# analog.net
KiCad netlist of a schematic drawn in Altium Designer
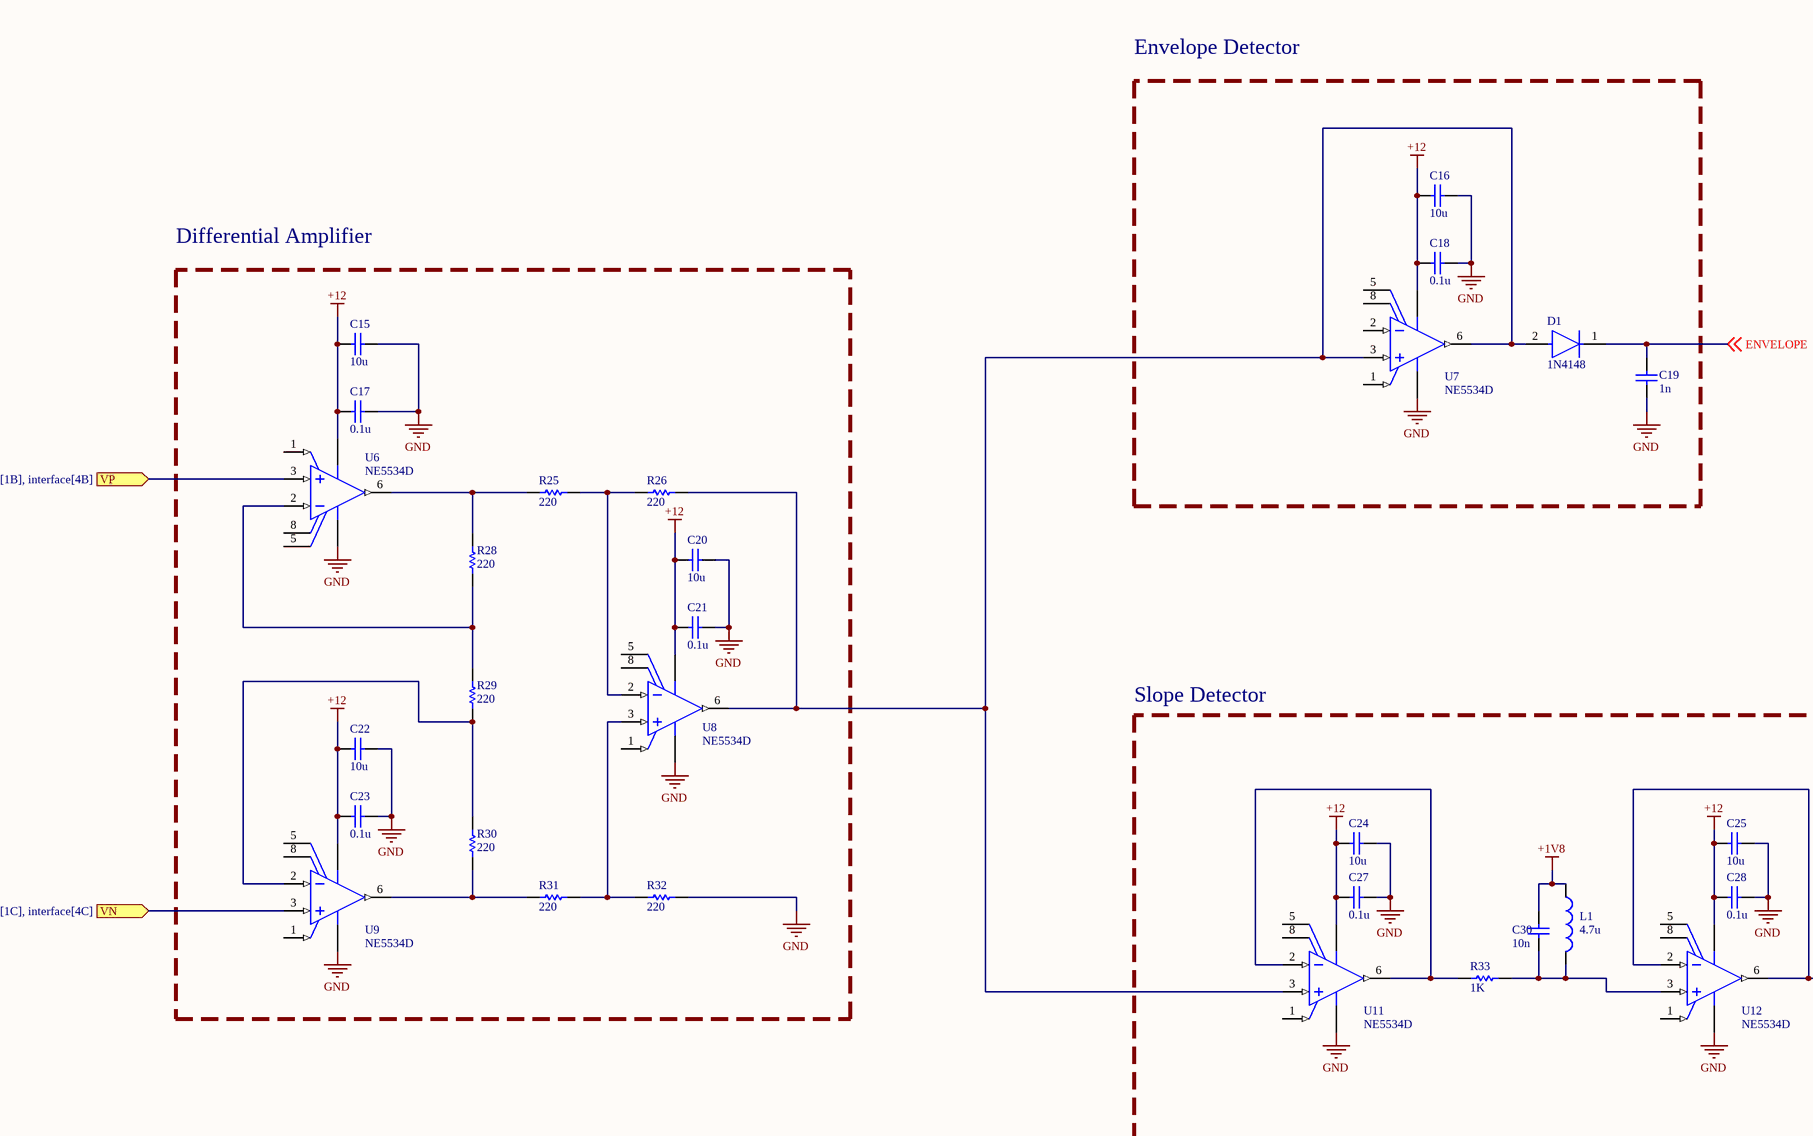
[diagram p0: analog.SchDoc, left]
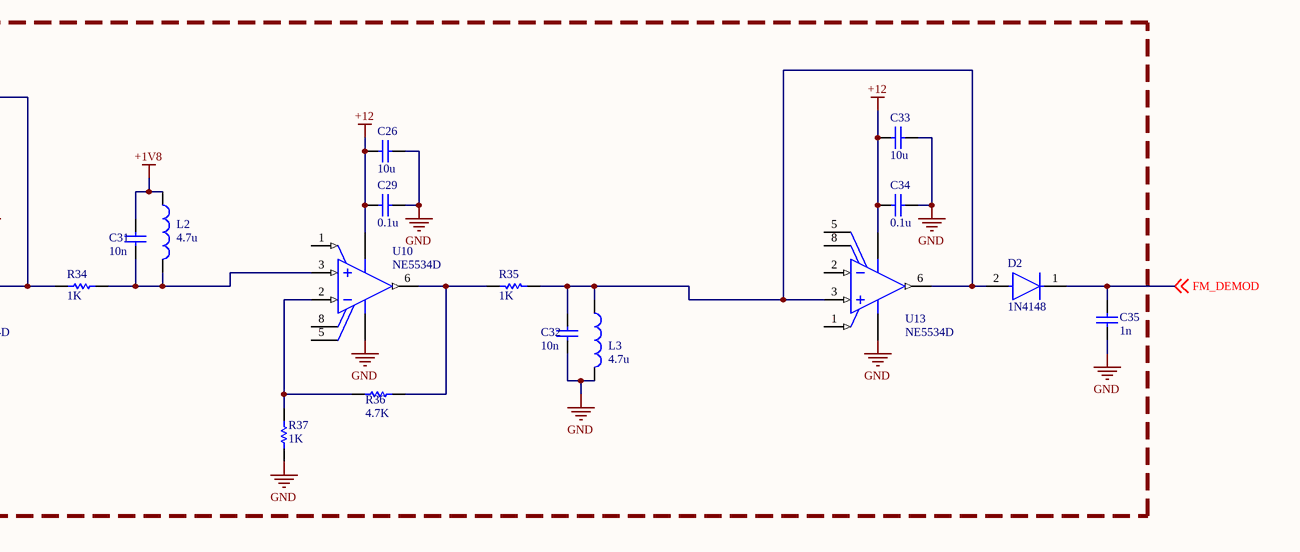
[diagram p1: analog.SchDoc, right]

(export (version "E")
  (design (tool "Eeschema 10.0.6"))
  (components
    (comp (ref "C15")
      (value "10u")
      (description "Capacitor")
      (libsource (lib "Simulation Generic Components") (part "Capacitor"))
    )
    (comp (ref "C16")
      (value "10u")
      (description "Capacitor")
      (libsource (lib "Simulation Generic Components") (part "Capacitor"))
    )
    (comp (ref "C17")
      (value "0.1u")
      (description "Capacitor")
      (libsource (lib "Simulation Generic Components") (part "Capacitor"))
    )
    (comp (ref "C18")
      (value "0.1u")
      (description "Capacitor")
      (libsource (lib "Simulation Generic Components") (part "Capacitor"))
    )
    (comp (ref "C19")
      (value "1n")
      (description "Capacitor")
      (libsource (lib "Simulation Generic Components") (part "Capacitor"))
    )
    (comp (ref "C20")
      (value "10u")
      (description "Capacitor")
      (libsource (lib "Simulation Generic Components") (part "Capacitor"))
    )
    (comp (ref "C21")
      (value "0.1u")
      (description "Capacitor")
      (libsource (lib "Simulation Generic Components") (part "Capacitor"))
    )
    (comp (ref "C22")
      (value "10u")
      (description "Capacitor")
      (libsource (lib "Simulation Generic Components") (part "Capacitor"))
    )
    (comp (ref "C23")
      (value "0.1u")
      (description "Capacitor")
      (libsource (lib "Simulation Generic Components") (part "Capacitor"))
    )
    (comp (ref "C24")
      (value "10u")
      (description "Capacitor")
      (libsource (lib "Simulation Generic Components") (part "Capacitor"))
    )
    (comp (ref "C25")
      (value "10u")
      (description "Capacitor")
      (libsource (lib "Simulation Generic Components") (part "Capacitor"))
    )
    (comp (ref "C26")
      (value "10u")
      (description "Capacitor")
      (libsource (lib "Simulation Generic Components") (part "Capacitor"))
    )
    (comp (ref "C27")
      (value "0.1u")
      (description "Capacitor")
      (libsource (lib "Simulation Generic Components") (part "Capacitor"))
    )
    (comp (ref "C28")
      (value "0.1u")
      (description "Capacitor")
      (libsource (lib "Simulation Generic Components") (part "Capacitor"))
    )
    (comp (ref "C29")
      (value "0.1u")
      (description "Capacitor")
      (libsource (lib "Simulation Generic Components") (part "Capacitor"))
    )
    (comp (ref "C30")
      (value "10n")
      (description "Capacitor")
      (libsource (lib "Simulation Generic Components") (part "Capacitor"))
    )
    (comp (ref "C31")
      (value "10n")
      (description "Capacitor")
      (libsource (lib "Simulation Generic Components") (part "Capacitor"))
    )
    (comp (ref "C32")
      (value "10n")
      (description "Capacitor")
      (libsource (lib "Simulation Generic Components") (part "Capacitor"))
    )
    (comp (ref "C33")
      (value "10u")
      (description "Capacitor")
      (libsource (lib "Simulation Generic Components") (part "Capacitor"))
    )
    (comp (ref "C34")
      (value "0.1u")
      (description "Capacitor")
      (libsource (lib "Simulation Generic Components") (part "Capacitor"))
    )
    (comp (ref "C35")
      (value "1n")
      (description "Capacitor")
      (libsource (lib "Simulation Generic Components") (part "Capacitor"))
    )
    (comp (ref "D1")
      (value "1N4148")
      (footprint "FP-017AG-MFG")
      (description "DIODE GEN PURP 100V 200MA DO35")
      (fields (field (name "VOLTAGE") "100V"))
      (libsource (lib "Altium Content Vault") (part "d7152d700b627762746794eb795d46e"))
    )
    (comp (ref "D2")
      (value "1N4148")
      (footprint "FP-017AG-MFG")
      (description "DIODE GEN PURP 100V 200MA DO35")
      (fields (field (name "VOLTAGE") "100V"))
      (libsource (lib "Altium Content Vault") (part "d7152d700b627762746794eb795d46e"))
    )
    (comp (ref "L1")
      (value "4.7u")
      (description "Inductor")
      (libsource (lib "Simulation Generic Components") (part "Inductor"))
    )
    (comp (ref "L2")
      (value "4.7u")
      (description "Inductor")
      (libsource (lib "Simulation Generic Components") (part "Inductor"))
    )
    (comp (ref "L3") (value "4.7u") (description "Inductor") (libsource (lib "") (part "Inductor_1")))
    (comp (ref "R25")
      (value "220")
      (description "Resistor")
      (libsource (lib "Simulation Generic Components") (part "Resistor"))
    )
    (comp (ref "R26")
      (value "220")
      (description "Resistor")
      (libsource (lib "Simulation Generic Components") (part "Resistor"))
    )
    (comp (ref "R28")
      (value "220")
      (description "Resistor")
      (libsource (lib "Simulation Generic Components") (part "Resistor"))
    )
    (comp (ref "R29")
      (value "220")
      (description "Resistor")
      (libsource (lib "Simulation Generic Components") (part "Resistor"))
    )
    (comp (ref "R30")
      (value "220")
      (description "Resistor")
      (libsource (lib "Simulation Generic Components") (part "Resistor"))
    )
    (comp (ref "R31")
      (value "220")
      (description "Resistor")
      (libsource (lib "Simulation Generic Components") (part "Resistor"))
    )
    (comp (ref "R32")
      (value "220")
      (description "Resistor")
      (libsource (lib "Simulation Generic Components") (part "Resistor"))
    )
    (comp (ref "R33")
      (value "1K")
      (description "Resistor")
      (libsource (lib "Simulation Generic Components") (part "Resistor"))
    )
    (comp (ref "R34")
      (value "1K")
      (description "Resistor")
      (libsource (lib "Simulation Generic Components") (part "Resistor"))
    )
    (comp (ref "R35")
      (value "1K")
      (description "Resistor")
      (libsource (lib "Simulation Generic Components") (part "Resistor"))
    )
    (comp (ref "R36")
      (value "4.7K")
      (description "Resistor")
      (libsource (lib "Simulation Generic Components") (part "Resistor"))
    )
    (comp (ref "R37")
      (value "1K")
      (description "Resistor")
      (libsource (lib "Simulation Generic Components") (part "Resistor"))
    )
    (comp (ref "U6")
      (value "NE5534D")
      (footprint "D0008A_N")
      (fields (field (name "MANUFACTURER") "Texas Instruments"))
      (libsource (lib "Altium Content Vault") (part "TI-XX5534X-X8"))
    )
    (comp (ref "U7")
      (value "NE5534D")
      (footprint "D0008A_N")
      (fields (field (name "MANUFACTURER") "Texas Instruments"))
      (libsource (lib "Altium Content Vault") (part "TI-XX5534X-X8"))
    )
    (comp (ref "U8")
      (value "NE5534D")
      (footprint "D0008A_N")
      (fields (field (name "MANUFACTURER") "Texas Instruments"))
      (libsource (lib "Altium Content Vault") (part "TI-XX5534X-X8"))
    )
    (comp (ref "U9")
      (value "NE5534D")
      (footprint "D0008A_N")
      (fields (field (name "MANUFACTURER") "Texas Instruments"))
      (libsource (lib "Altium Content Vault") (part "TI-XX5534X-X8"))
    )
    (comp (ref "U10")
      (value "NE5534D")
      (footprint "D0008A_N")
      (fields (field (name "MANUFACTURER") "Texas Instruments"))
      (libsource (lib "Altium Content Vault") (part "TI-XX5534X-X8"))
    )
    (comp (ref "U11")
      (value "NE5534D")
      (footprint "D0008A_N")
      (fields (field (name "MANUFACTURER") "Texas Instruments"))
      (libsource (lib "Altium Content Vault") (part "TI-XX5534X-X8"))
    )
    (comp (ref "U12")
      (value "NE5534D")
      (footprint "D0008A_N")
      (fields (field (name "MANUFACTURER") "Texas Instruments"))
      (libsource (lib "Altium Content Vault") (part "TI-XX5534X-X8"))
    )
    (comp (ref "U13")
      (value "NE5534D")
      (footprint "D0008A_N")
      (fields (field (name "MANUFACTURER") "Texas Instruments"))
      (libsource (lib "Altium Content Vault") (part "TI-XX5534X-X8"))
    )
  )
  (nets
    (net (code "1") (name "+1V8") (class "Default")
      (node (ref "C30") (pin "2") (pinfunction "2_2") (pintype "passive"))
      (node (ref "C31") (pin "2") (pinfunction "2_2") (pintype "passive"))
      (node (ref "L1") (pin "1") (pinfunction "1_1") (pintype "passive"))
      (node (ref "L2") (pin "1") (pinfunction "1_1") (pintype "passive"))
    )
    (net (code "2") (name "+12") (class "Default")
      (node (ref "C15") (pin "1") (pinfunction "1_1") (pintype "passive"))
      (node (ref "C16") (pin "1") (pinfunction "1_1") (pintype "passive"))
      (node (ref "C17") (pin "1") (pinfunction "1_1") (pintype "passive"))
      (node (ref "C18") (pin "1") (pinfunction "1_1") (pintype "passive"))
      (node (ref "C20") (pin "1") (pinfunction "1_1") (pintype "passive"))
      (node (ref "C21") (pin "1") (pinfunction "1_1") (pintype "passive"))
      (node (ref "C22") (pin "1") (pinfunction "1_1") (pintype "passive"))
      (node (ref "C23") (pin "1") (pinfunction "1_1") (pintype "passive"))
      (node (ref "C24") (pin "1") (pinfunction "1_1") (pintype "passive"))
      (node (ref "C25") (pin "1") (pinfunction "1_1") (pintype "passive"))
      (node (ref "C26") (pin "1") (pinfunction "1_1") (pintype "passive"))
      (node (ref "C27") (pin "1") (pinfunction "1_1") (pintype "passive"))
      (node (ref "C28") (pin "1") (pinfunction "1_1") (pintype "passive"))
      (node (ref "C29") (pin "1") (pinfunction "1_1") (pintype "passive"))
      (node (ref "C33") (pin "1") (pinfunction "1_1") (pintype "passive"))
      (node (ref "C34") (pin "1") (pinfunction "1_1") (pintype "passive"))
      (node (ref "U10") (pin "4") (pinfunction "VCC-_4") (pintype "power_in"))
      (node (ref "U11") (pin "7") (pinfunction "VCC+_7") (pintype "power_in"))
      (node (ref "U12") (pin "7") (pinfunction "VCC+_7") (pintype "power_in"))
      (node (ref "U13") (pin "7") (pinfunction "VCC+_7") (pintype "power_in"))
      (node (ref "U6") (pin "4") (pinfunction "VCC-_4") (pintype "power_in"))
      (node (ref "U7") (pin "7") (pinfunction "VCC+_7") (pintype "power_in"))
      (node (ref "U8") (pin "7") (pinfunction "VCC+_7") (pintype "power_in"))
      (node (ref "U9") (pin "7") (pinfunction "VCC+_7") (pintype "power_in"))
    )
    (net (code "3") (name "/VN") (class "Default")
      (node (ref "U9") (pin "3") (pinfunction "IN+_3") (pintype "input"))
    )
    (net (code "4") (name "/VP") (class "Default")
      (node (ref "U6") (pin "3") (pinfunction "IN+_3") (pintype "input"))
    )
    (net (code "5") (name "ENVELOPE") (class "Default")
      (node (ref "C19") (pin "2") (pinfunction "2_2") (pintype "passive"))
      (node (ref "D1") (pin "1") (pinfunction "C_1") (pintype "passive"))
    )
    (net (code "6") (name "FM_DEMOD") (class "Default")
      (node (ref "C35") (pin "2") (pinfunction "2_2") (pintype "passive"))
      (node (ref "D2") (pin "1") (pinfunction "C_1") (pintype "passive"))
    )
    (net (code "7") (name "GND") (class "Default")
      (node (ref "C15") (pin "2") (pinfunction "2_2") (pintype "passive"))
      (node (ref "C16") (pin "2") (pinfunction "2_2") (pintype "passive"))
      (node (ref "C17") (pin "2") (pinfunction "2_2") (pintype "passive"))
      (node (ref "C18") (pin "2") (pinfunction "2_2") (pintype "passive"))
      (node (ref "C19") (pin "1") (pinfunction "1_1") (pintype "passive"))
      (node (ref "C20") (pin "2") (pinfunction "2_2") (pintype "passive"))
      (node (ref "C21") (pin "2") (pinfunction "2_2") (pintype "passive"))
      (node (ref "C22") (pin "2") (pinfunction "2_2") (pintype "passive"))
      (node (ref "C23") (pin "2") (pinfunction "2_2") (pintype "passive"))
      (node (ref "C24") (pin "2") (pinfunction "2_2") (pintype "passive"))
      (node (ref "C25") (pin "2") (pinfunction "2_2") (pintype "passive"))
      (node (ref "C26") (pin "2") (pinfunction "2_2") (pintype "passive"))
      (node (ref "C27") (pin "2") (pinfunction "2_2") (pintype "passive"))
      (node (ref "C28") (pin "2") (pinfunction "2_2") (pintype "passive"))
      (node (ref "C29") (pin "2") (pinfunction "2_2") (pintype "passive"))
      (node (ref "C32") (pin "2") (pinfunction "2_2") (pintype "passive"))
      (node (ref "C33") (pin "2") (pinfunction "2_2") (pintype "passive"))
      (node (ref "C34") (pin "2") (pinfunction "2_2") (pintype "passive"))
      (node (ref "C35") (pin "1") (pinfunction "1_1") (pintype "passive"))
      (node (ref "L3") (pin "1") (pinfunction "1_1") (pintype "passive"))
      (node (ref "R32") (pin "1") (pinfunction "1_1") (pintype "passive"))
      (node (ref "R37") (pin "2") (pinfunction "2_2") (pintype "passive"))
      (node (ref "U10") (pin "7") (pinfunction "VCC+_7") (pintype "power_in"))
      (node (ref "U11") (pin "4") (pinfunction "VCC-_4") (pintype "power_in"))
      (node (ref "U12") (pin "4") (pinfunction "VCC-_4") (pintype "power_in"))
      (node (ref "U13") (pin "4") (pinfunction "VCC-_4") (pintype "power_in"))
      (node (ref "U6") (pin "7") (pinfunction "VCC+_7") (pintype "power_in"))
      (node (ref "U7") (pin "4") (pinfunction "VCC-_4") (pintype "power_in"))
      (node (ref "U8") (pin "4") (pinfunction "VCC-_4") (pintype "power_in"))
      (node (ref "U9") (pin "4") (pinfunction "VCC-_4") (pintype "power_in"))
    )
    (net (code "8") (name "Net-(D1-A)") (class "Default")
      (node (ref "D1") (pin "2") (pinfunction "A_2") (pintype "passive"))
      (node (ref "R26") (pin "1") (pinfunction "1_1") (pintype "passive"))
      (node (ref "U11") (pin "3") (pinfunction "IN+_3") (pintype "input"))
      (node (ref "U7") (pin "3") (pinfunction "IN+_3") (pintype "input"))
      (node (ref "U7") (pin "6") (pinfunction "OUT_6") (pintype "output"))
      (node (ref "U8") (pin "6") (pinfunction "OUT_6") (pintype "output"))
    )
    (net (code "9") (name "Net-(D2-A)") (class "Default")
      (node (ref "C32") (pin "1") (pinfunction "1_1") (pintype "passive"))
      (node (ref "D2") (pin "2") (pinfunction "A_2") (pintype "passive"))
      (node (ref "L3") (pin "2") (pinfunction "2_2") (pintype "passive"))
      (node (ref "R35") (pin "1") (pinfunction "1_1") (pintype "passive"))
      (node (ref "U13") (pin "3") (pinfunction "IN+_3") (pintype "input"))
      (node (ref "U13") (pin "6") (pinfunction "OUT_6") (pintype "output"))
    )
    (net (code "10") (name "Net-(U6-IN-)") (class "Default")
      (node (ref "R28") (pin "1") (pinfunction "1_1") (pintype "passive"))
      (node (ref "R29") (pin "2") (pinfunction "2_2") (pintype "passive"))
      (node (ref "U6") (pin "2") (pinfunction "IN-_2") (pintype "input"))
    )
    (net (code "11") (name "Net-(U6-OUT)") (class "Default")
      (node (ref "R25") (pin "2") (pinfunction "2_2") (pintype "passive"))
      (node (ref "R28") (pin "2") (pinfunction "2_2") (pintype "passive"))
      (node (ref "U6") (pin "6") (pinfunction "OUT_6") (pintype "output"))
    )
    (net (code "12") (name "Net-(U8-IN+)") (class "Default")
      (node (ref "R31") (pin "1") (pinfunction "1_1") (pintype "passive"))
      (node (ref "R32") (pin "2") (pinfunction "2_2") (pintype "passive"))
      (node (ref "U8") (pin "3") (pinfunction "IN+_3") (pintype "input"))
    )
    (net (code "13") (name "Net-(U8-IN-)") (class "Default")
      (node (ref "R25") (pin "1") (pinfunction "1_1") (pintype "passive"))
      (node (ref "R26") (pin "2") (pinfunction "2_2") (pintype "passive"))
      (node (ref "U8") (pin "2") (pinfunction "IN-_2") (pintype "input"))
    )
    (net (code "14") (name "Net-(U9-IN-)") (class "Default")
      (node (ref "R29") (pin "1") (pinfunction "1_1") (pintype "passive"))
      (node (ref "R30") (pin "2") (pinfunction "2_2") (pintype "passive"))
      (node (ref "U9") (pin "2") (pinfunction "IN-_2") (pintype "input"))
    )
    (net (code "15") (name "Net-(U9-OUT)") (class "Default")
      (node (ref "R30") (pin "1") (pinfunction "1_1") (pintype "passive"))
      (node (ref "R31") (pin "2") (pinfunction "2_2") (pintype "passive"))
      (node (ref "U9") (pin "6") (pinfunction "OUT_6") (pintype "output"))
    )
    (net (code "16") (name "Net-(U10-IN+)") (class "Default")
      (node (ref "C31") (pin "1") (pinfunction "1_1") (pintype "passive"))
      (node (ref "L2") (pin "2") (pinfunction "2_2") (pintype "passive"))
      (node (ref "R34") (pin "1") (pinfunction "1_1") (pintype "passive"))
      (node (ref "U10") (pin "3") (pinfunction "IN+_3") (pintype "input"))
    )
    (net (code "17") (name "Net-(U10-IN-)") (class "Default")
      (node (ref "R36") (pin "2") (pinfunction "2_2") (pintype "passive"))
      (node (ref "R37") (pin "1") (pinfunction "1_1") (pintype "passive"))
      (node (ref "U10") (pin "2") (pinfunction "IN-_2") (pintype "input"))
    )
    (net (code "18") (name "Net-(U10-OUT)") (class "Default")
      (node (ref "R35") (pin "2") (pinfunction "2_2") (pintype "passive"))
      (node (ref "R36") (pin "1") (pinfunction "1_1") (pintype "passive"))
      (node (ref "U10") (pin "6") (pinfunction "OUT_6") (pintype "output"))
    )
    (net (code "19") (name "Net-(U11-IN-)") (class "Default")
      (node (ref "R33") (pin "2") (pinfunction "2_2") (pintype "passive"))
      (node (ref "U11") (pin "2") (pinfunction "IN-_2") (pintype "input"))
      (node (ref "U11") (pin "6") (pinfunction "OUT_6") (pintype "output"))
    )
    (net (code "20") (name "Net-(U12-IN+)") (class "Default")
      (node (ref "C30") (pin "1") (pinfunction "1_1") (pintype "passive"))
      (node (ref "L1") (pin "2") (pinfunction "2_2") (pintype "passive"))
      (node (ref "R33") (pin "1") (pinfunction "1_1") (pintype "passive"))
      (node (ref "U12") (pin "3") (pinfunction "IN+_3") (pintype "input"))
    )
    (net (code "21") (name "Net-(U12-IN-)") (class "Default")
      (node (ref "R34") (pin "2") (pinfunction "2_2") (pintype "passive"))
      (node (ref "U12") (pin "2") (pinfunction "IN-_2") (pintype "input"))
      (node (ref "U12") (pin "6") (pinfunction "OUT_6") (pintype "output"))
    )
    (net (code "22") (name "unconnected-(U6-BALANCE-Pad1)") (class "Default")
      (node (ref "U6") (pin "1") (pinfunction "BALANCE_1") (pintype "input"))
    )
    (net (code "23") (name "unconnected-(U6-COMP-Pad5)") (class "Default")
      (node (ref "U6") (pin "5") (pinfunction "COMP_5") (pintype "passive"))
    )
    (net (code "24") (name "unconnected-(U6-COMP{slash}BAL-Pad8)") (class "Default")
      (node (ref "U6") (pin "8") (pinfunction "COMP/BAL_8") (pintype "passive"))
    )
    (net (code "25") (name "unconnected-(U7-BALANCE-Pad1)") (class "Default")
      (node (ref "U7") (pin "1") (pinfunction "BALANCE_1") (pintype "input"))
    )
    (net (code "26") (name "unconnected-(U7-COMP-Pad5)") (class "Default")
      (node (ref "U7") (pin "5") (pinfunction "COMP_5") (pintype "passive"))
    )
    (net (code "27") (name "unconnected-(U7-COMP{slash}BAL-Pad8)") (class "Default")
      (node (ref "U7") (pin "8") (pinfunction "COMP/BAL_8") (pintype "passive"))
    )
    (net (code "28") (name "unconnected-(U7-IN--Pad2)") (class "Default")
      (node (ref "U7") (pin "2") (pinfunction "IN-_2") (pintype "input"))
    )
    (net (code "29") (name "unconnected-(U8-BALANCE-Pad1)") (class "Default")
      (node (ref "U8") (pin "1") (pinfunction "BALANCE_1") (pintype "input"))
    )
    (net (code "30") (name "unconnected-(U8-COMP-Pad5)") (class "Default")
      (node (ref "U8") (pin "5") (pinfunction "COMP_5") (pintype "passive"))
    )
    (net (code "31") (name "unconnected-(U8-COMP{slash}BAL-Pad8)") (class "Default")
      (node (ref "U8") (pin "8") (pinfunction "COMP/BAL_8") (pintype "passive"))
    )
    (net (code "32") (name "unconnected-(U9-BALANCE-Pad1)") (class "Default")
      (node (ref "U9") (pin "1") (pinfunction "BALANCE_1") (pintype "input"))
    )
    (net (code "33") (name "unconnected-(U9-COMP-Pad5)") (class "Default")
      (node (ref "U9") (pin "5") (pinfunction "COMP_5") (pintype "passive"))
    )
    (net (code "34") (name "unconnected-(U9-COMP{slash}BAL-Pad8)") (class "Default")
      (node (ref "U9") (pin "8") (pinfunction "COMP/BAL_8") (pintype "passive"))
    )
    (net (code "35") (name "unconnected-(U10-BALANCE-Pad1)") (class "Default")
      (node (ref "U10") (pin "1") (pinfunction "BALANCE_1") (pintype "input"))
    )
    (net (code "36") (name "unconnected-(U10-COMP-Pad5)") (class "Default")
      (node (ref "U10") (pin "5") (pinfunction "COMP_5") (pintype "passive"))
    )
    (net (code "37") (name "unconnected-(U10-COMP{slash}BAL-Pad8)") (class "Default")
      (node (ref "U10") (pin "8") (pinfunction "COMP/BAL_8") (pintype "passive"))
    )
    (net (code "38") (name "unconnected-(U11-BALANCE-Pad1)") (class "Default")
      (node (ref "U11") (pin "1") (pinfunction "BALANCE_1") (pintype "input"))
    )
    (net (code "39") (name "unconnected-(U11-COMP-Pad5)") (class "Default")
      (node (ref "U11") (pin "5") (pinfunction "COMP_5") (pintype "passive"))
    )
    (net (code "40") (name "unconnected-(U11-COMP{slash}BAL-Pad8)") (class "Default")
      (node (ref "U11") (pin "8") (pinfunction "COMP/BAL_8") (pintype "passive"))
    )
    (net (code "41") (name "unconnected-(U12-BALANCE-Pad1)") (class "Default")
      (node (ref "U12") (pin "1") (pinfunction "BALANCE_1") (pintype "input"))
    )
    (net (code "42") (name "unconnected-(U12-COMP-Pad5)") (class "Default")
      (node (ref "U12") (pin "5") (pinfunction "COMP_5") (pintype "passive"))
    )
    (net (code "43") (name "unconnected-(U12-COMP{slash}BAL-Pad8)") (class "Default")
      (node (ref "U12") (pin "8") (pinfunction "COMP/BAL_8") (pintype "passive"))
    )
    (net (code "44") (name "unconnected-(U13-BALANCE-Pad1)") (class "Default")
      (node (ref "U13") (pin "1") (pinfunction "BALANCE_1") (pintype "input"))
    )
    (net (code "45") (name "unconnected-(U13-COMP-Pad5)") (class "Default")
      (node (ref "U13") (pin "5") (pinfunction "COMP_5") (pintype "passive"))
    )
    (net (code "46") (name "unconnected-(U13-COMP{slash}BAL-Pad8)") (class "Default")
      (node (ref "U13") (pin "8") (pinfunction "COMP/BAL_8") (pintype "passive"))
    )
    (net (code "47") (name "unconnected-(U13-IN--Pad2)") (class "Default")
      (node (ref "U13") (pin "2") (pinfunction "IN-_2") (pintype "input"))
    )
  )
)
